# Preamplifier.net
KiCad netlist of a schematic drawn in Altium Designer
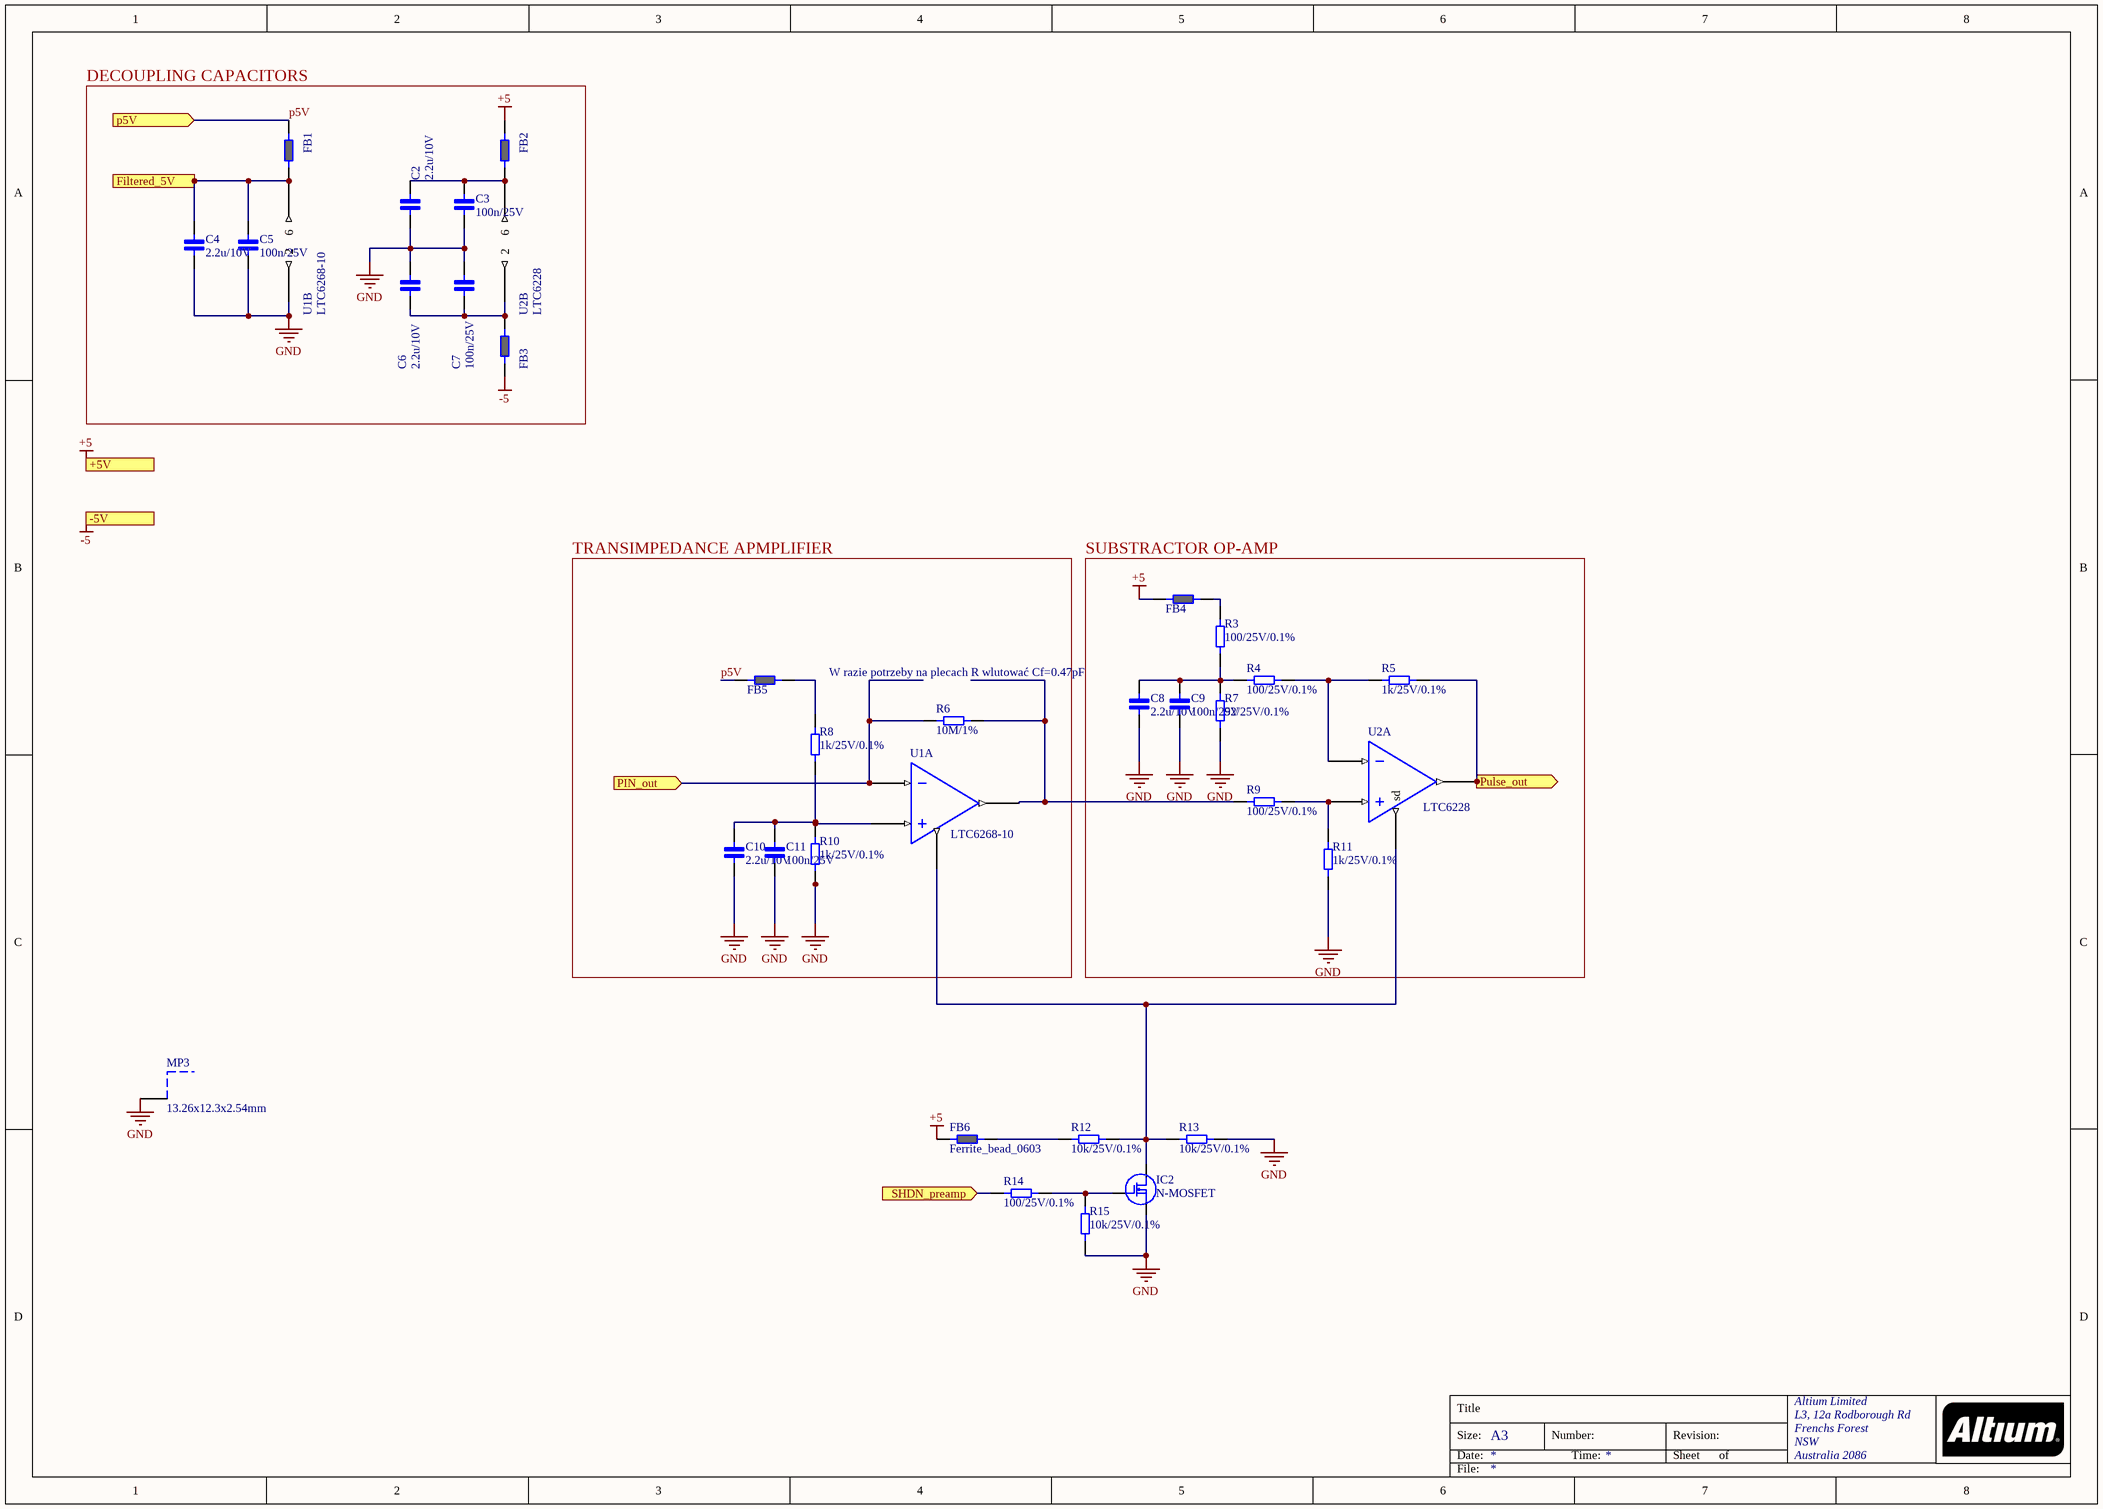
[diagram p0: Preamplifier.SchDoc]

(export (version "E")
  (design (tool "Eeschema 10.0.6"))
  (components
    (comp (ref "C2")
      (value "2.2u/10V")
      (footprint "Cap_0402")
      (description "Ceramic Capacitor 2.2uF / 0402 / 10V / ±5%, Wurth Elektronik MLCC")
      (libsource (lib "Cubesat_lib") (part "Cap_0402_2.2u"))
    )
    (comp (ref "C3")
      (value "100n/25V")
      (footprint "Cap_0402")
      (description "Ceramic Capacitor 100n / 0402 / 25V / ±5%, Wurth Elektronik MLCC")
      (libsource (lib "Cubesat_lib") (part "Cap_0402_100n"))
    )
    (comp (ref "C4")
      (value "2.2u/10V")
      (footprint "Cap_0402")
      (description "Ceramic Capacitor 2.2uF / 0402 / 10V / ±5%, Wurth Elektronik MLCC")
      (libsource (lib "Cubesat_lib") (part "Cap_0402_2.2u"))
    )
    (comp (ref "C5")
      (value "100n/25V")
      (footprint "Cap_0402")
      (description "Ceramic Capacitor 100n / 0402 / 25V / ±5%, Wurth Elektronik MLCC")
      (libsource (lib "Cubesat_lib") (part "Cap_0402_100n"))
    )
    (comp (ref "C6")
      (value "2.2u/10V")
      (footprint "Cap_0402")
      (description "Ceramic Capacitor 2.2uF / 0402 / 10V / ±5%, Wurth Elektronik MLCC")
      (libsource (lib "Cubesat_lib") (part "Cap_0402_2.2u"))
    )
    (comp (ref "C7")
      (value "100n/25V")
      (footprint "Cap_0402")
      (description "Ceramic Capacitor 100n / 0402 / 25V / ±5%, Wurth Elektronik MLCC")
      (libsource (lib "Cubesat_lib") (part "Cap_0402_100n"))
    )
    (comp (ref "C8")
      (value "2.2u/10V")
      (footprint "Cap_0402")
      (description "Ceramic Capacitor 2.2uF / 0402 / 10V / ±5%, Wurth Elektronik MLCC")
      (libsource (lib "Cubesat_lib") (part "Cap_0402_2.2u"))
    )
    (comp (ref "C9")
      (value "100n/25V")
      (footprint "Cap_0402")
      (description "Ceramic Capacitor 100n / 0402 / 25V / ±5%, Wurth Elektronik MLCC")
      (libsource (lib "Cubesat_lib") (part "Cap_0402_100n"))
    )
    (comp (ref "C10")
      (value "2.2u/10V")
      (footprint "Cap_0402")
      (description "Ceramic Capacitor 2.2uF / 0402 / 10V / ±5%, Wurth Elektronik MLCC")
      (libsource (lib "Cubesat_lib") (part "Cap_0402_2.2u"))
    )
    (comp (ref "C11")
      (value "100n/25V")
      (footprint "Cap_0402")
      (description "Ceramic Capacitor 100n / 0402 / 25V / ±5%, Wurth Elektronik MLCC")
      (libsource (lib "Cubesat_lib") (part "Cap_0402_100n"))
    )
    (comp (ref "FB1")
      (value "Ferrite_bead_0603")
      (footprint "Ferrite_0603")
      (description "Ferrite bead")
      (libsource (lib "") (part "Ferrite_bead_0603_2"))
    )
    (comp (ref "FB2")
      (value "Ferrite_bead_0603")
      (footprint "Ferrite_0603")
      (description "Ferrite bead")
      (libsource (lib "") (part "Ferrite_bead_0603_2"))
    )
    (comp (ref "FB3")
      (value "Ferrite_bead_0603")
      (footprint "Ferrite_0603")
      (description "Ferrite bead")
      (libsource (lib "") (part "Ferrite_bead_0603_2"))
    )
    (comp (ref "FB4")
      (value "Ferrite_bead_0603")
      (footprint "Ferrite_0603")
      (description "Ferrite bead")
      (libsource (lib "") (part "Ferrite_bead_0603_1"))
    )
    (comp (ref "FB5")
      (value "Ferrite_bead_0603")
      (footprint "Ferrite_0603")
      (description "Ferrite bead")
      (libsource (lib "") (part "Ferrite_bead_0603_1"))
    )
    (comp (ref "FB6")
      (value "Ferrite_bead_0603")
      (footprint "Ferrite_0603")
      (description "Ferrite bead")
      (libsource (lib "Cubesat_lib") (part "Ferrite_bead_0603"))
    )
    (comp (ref "IC2")
      (value "N-MOSFET")
      (footprint "SOT23-3")
      (description "n-mosfet 50V, low threshold")
      (fields
        (field (name "MANUFACTURER") "NXP Semiconductors")
        (field (name "MANUFACTURER PART NUMBER") "BF861C")
      )
      (libsource (lib "Cubesat_lib") (part "BSS138K"))
    )
    (comp (ref "MP3")
      (value "13.26x12.3x2.54mm")
      (footprint "3610213126S")
      (description "WE-SHC Shielding Cabinet, SMT Frame, Tin Plated, Tape and Reel, 13.26x12.3x2.54mm")
      (fields
        (field (name "MANUFACTURER") "Wurth Elektronik")
        (field (name "MANUFACTURER PART NUMBER") "3610213126S")
      )
      (libsource (lib "shield") (part "3610213126S"))
    )
    (comp (ref "R3")
      (value "100/25V/0.1%")
      (footprint "RES_0402")
      (description "Vishay, thin film resistor 100/25V/0.1%")
      (libsource (lib "") (part "Res_0402_100_1"))
    )
    (comp (ref "R4")
      (value "100/25V/0.1%")
      (footprint "RES_0402")
      (description "Vishay, thin film resistor 100/25V/0.1%")
      (libsource (lib "Cubesat_lib") (part "Res_0402_100"))
    )
    (comp (ref "R5")
      (value "1k/25V/0.1%")
      (footprint "RES_0402")
      (description "Vishay, thin film resistor 1k/25V/0.1%")
      (libsource (lib "") (part "Res_0402_1k_1"))
    )
    (comp (ref "R6")
      (value "10M/1%")
      (footprint "RES_1206_prec")
      (description "Res Thin Film 1206 10M Ohm 0.1% 0.33W(1/3W) ±50ppm/C Sulfur Resistant Pad SMD T/R")
      (fields
        (field (name "MANUFACTURER") "Vishay Dale")
        (field (name "MANUFACTURER PART NUMBER") "P1206H1005BGT")
      )
      (libsource (lib "Cubesat_lib") (part "Prec_res_10M"))
    )
    (comp (ref "R7")
      (value "92/25V/0.1%")
      (footprint "RES_0402")
      (description "Vishay, thin film resistor 92/25V/0.1%")
      (libsource (lib "Cubesat_lib") (part "Res_0402_92"))
    )
    (comp (ref "R8")
      (value "1k/25V/0.1%")
      (footprint "RES_0402")
      (description "Vishay, thin film resistor 1k/25V/0.1%")
      (libsource (lib "Cubesat_lib") (part "Res_0402_1k"))
    )
    (comp (ref "R9")
      (value "100/25V/0.1%")
      (footprint "RES_0402")
      (description "Vishay, thin film resistor 100/25V/0.1%")
      (libsource (lib "Cubesat_lib") (part "Res_0402_100"))
    )
    (comp (ref "R10")
      (value "1k/25V/0.1%")
      (footprint "RES_0402")
      (description "Vishay, thin film resistor 1k/25V/0.1%")
      (libsource (lib "Cubesat_lib") (part "Res_0402_1k"))
    )
    (comp (ref "R11")
      (value "1k/25V/0.1%")
      (footprint "RES_0402")
      (description "Vishay, thin film resistor 1k/25V/0.1%")
      (libsource (lib "Cubesat_lib") (part "Res_0402_1k"))
    )
    (comp (ref "R12")
      (value "10k/25V/0.1%")
      (footprint "RES_0402")
      (description "Vishay, thin film resistor 10k/25V/0.1%")
      (libsource (lib "Cubesat_lib") (part "Res_0402_10k"))
    )
    (comp (ref "R13")
      (value "10k/25V/0.1%")
      (footprint "RES_0402")
      (description "Vishay, thin film resistor 10k/25V/0.1%")
      (libsource (lib "Cubesat_lib") (part "Res_0402_10k"))
    )
    (comp (ref "R14")
      (value "100/25V/0.1%")
      (footprint "RES_0402")
      (description "Vishay, thin film resistor 100/25V/0.1%")
      (libsource (lib "Cubesat_lib") (part "Res_0402_100"))
    )
    (comp (ref "R15")
      (value "10k/25V/0.1%")
      (footprint "RES_0402")
      (description "Vishay, thin film resistor 10k/25V/0.1%")
      (libsource (lib "") (part "Res_0402_10k_1"))
    )
    (comp (ref "U1")
      (value "LTC6268-10")
      (footprint "SOT-23-6")
      (description "4 ghz, ultra-low noise opamp")
      (libsource (lib "Cubesat_lib") (part "LTC6268"))
    )
    (comp (ref "U2")
      (value "LTC6228")
      (footprint "SOT-23-6")
      (description "0.88nV/√Hz 730MHz, 500V/µs,\r\nLow Distortion Rail-to-Rail Output Op\r\nAmps with Shutdown")
      (libsource (lib "Cubesat_lib") (part "LTC6228"))
    )
  )
  (nets
    (net (code "1") (name "+5") (class "Default")
      (node (ref "FB2") (pin "2") (pinfunction "2_2") (pintype "passive"))
      (node (ref "FB4") (pin "2") (pinfunction "2_2") (pintype "passive"))
      (node (ref "FB6") (pin "1") (pinfunction "1_1") (pintype "passive"))
    )
    (net (code "2") (name "-5") (class "Default")
      (node (ref "FB3") (pin "1") (pinfunction "1_1") (pintype "passive"))
    )
    (net (code "3") (name "/Filtered_5V") (class "Default")
      (node (ref "C4") (pin "2") (pinfunction "2_2") (pintype "passive"))
      (node (ref "C5") (pin "2") (pinfunction "2_2") (pintype "passive"))
      (node (ref "FB1") (pin "1") (pinfunction "1_1") (pintype "passive"))
      (node (ref "U1") (pin "6") (pinfunction "6_6") (pintype "output"))
    )
    (net (code "4") (name "/PIN_out") (class "Default")
      (node (ref "R6") (pin "1") (pinfunction "1_1") (pintype "passive"))
      (node (ref "U1") (pin "4") (pinfunction "4_4") (pintype "input"))
    )
    (net (code "5") (name "/Pulse_out") (class "Default")
      (node (ref "R5") (pin "2") (pinfunction "2_2") (pintype "passive"))
      (node (ref "U2") (pin "1") (pinfunction "1_1") (pintype "output"))
    )
    (net (code "6") (name "/SHDN_preamp") (class "Default")
      (node (ref "R14") (pin "1") (pinfunction "1_1") (pintype "passive"))
    )
    (net (code "7") (name "/p5V") (class "Default")
      (node (ref "FB1") (pin "2") (pinfunction "2_2") (pintype "passive"))
      (node (ref "FB5") (pin "2") (pinfunction "2_2") (pintype "passive"))
    )
    (net (code "8") (name "GND") (class "Default")
      (node (ref "C10") (pin "1") (pinfunction "1_1") (pintype "passive"))
      (node (ref "C11") (pin "1") (pinfunction "1_1") (pintype "passive"))
      (node (ref "C2") (pin "1") (pinfunction "1_1") (pintype "passive"))
      (node (ref "C3") (pin "1") (pinfunction "1_1") (pintype "passive"))
      (node (ref "C4") (pin "1") (pinfunction "1_1") (pintype "passive"))
      (node (ref "C5") (pin "1") (pinfunction "1_1") (pintype "passive"))
      (node (ref "C6") (pin "2") (pinfunction "2_2") (pintype "passive"))
      (node (ref "C7") (pin "2") (pinfunction "2_2") (pintype "passive"))
      (node (ref "C8") (pin "1") (pinfunction "1_1") (pintype "passive"))
      (node (ref "C9") (pin "1") (pinfunction "1_1") (pintype "passive"))
      (node (ref "IC2") (pin "2") (pinfunction "S_2") (pintype "passive"))
      (node (ref "MP3") (pin "1") (pinfunction "1_1") (pintype "passive"))
      (node (ref "R10") (pin "1") (pinfunction "1_1") (pintype "passive"))
      (node (ref "R11") (pin "1") (pinfunction "1_1") (pintype "passive"))
      (node (ref "R13") (pin "2") (pinfunction "2_2") (pintype "passive"))
      (node (ref "R15") (pin "1") (pinfunction "1_1") (pintype "passive"))
      (node (ref "R7") (pin "1") (pinfunction "1_1") (pintype "passive"))
      (node (ref "U1") (pin "2") (pinfunction "2_2") (pintype "output"))
    )
    (net (code "9") (name "Net-(C2-Pad2)") (class "Default")
      (node (ref "C2") (pin "2") (pinfunction "2_2") (pintype "passive"))
      (node (ref "C3") (pin "2") (pinfunction "2_2") (pintype "passive"))
      (node (ref "FB2") (pin "1") (pinfunction "1_1") (pintype "passive"))
      (node (ref "U2") (pin "6") (pinfunction "6_6") (pintype "output"))
    )
    (net (code "10") (name "Net-(C6-Pad1)") (class "Default")
      (node (ref "C6") (pin "1") (pinfunction "1_1") (pintype "passive"))
      (node (ref "C7") (pin "1") (pinfunction "1_1") (pintype "passive"))
      (node (ref "FB3") (pin "2") (pinfunction "2_2") (pintype "passive"))
      (node (ref "U2") (pin "2") (pinfunction "2_2") (pintype "output"))
    )
    (net (code "11") (name "Net-(C8-Pad2)") (class "Default")
      (node (ref "C8") (pin "2") (pinfunction "2_2") (pintype "passive"))
      (node (ref "C9") (pin "2") (pinfunction "2_2") (pintype "passive"))
      (node (ref "R3") (pin "1") (pinfunction "1_1") (pintype "passive"))
      (node (ref "R4") (pin "1") (pinfunction "1_1") (pintype "passive"))
      (node (ref "R7") (pin "2") (pinfunction "2_2") (pintype "passive"))
    )
    (net (code "12") (name "Net-(C10-Pad2)") (class "Default")
      (node (ref "C10") (pin "2") (pinfunction "2_2") (pintype "passive"))
      (node (ref "C11") (pin "2") (pinfunction "2_2") (pintype "passive"))
      (node (ref "R10") (pin "2") (pinfunction "2_2") (pintype "passive"))
      (node (ref "R8") (pin "1") (pinfunction "1_1") (pintype "passive"))
      (node (ref "U1") (pin "3") (pinfunction "3_3") (pintype "input"))
    )
    (net (code "13") (name "Net-(FB4-Pad1)") (class "Default")
      (node (ref "FB4") (pin "1") (pinfunction "1_1") (pintype "passive"))
      (node (ref "R3") (pin "2") (pinfunction "2_2") (pintype "passive"))
    )
    (net (code "14") (name "Net-(FB5-Pad1)") (class "Default")
      (node (ref "FB5") (pin "1") (pinfunction "1_1") (pintype "passive"))
      (node (ref "R8") (pin "2") (pinfunction "2_2") (pintype "passive"))
    )
    (net (code "15") (name "Net-(FB6-Pad2)") (class "Default")
      (node (ref "FB6") (pin "2") (pinfunction "2_2") (pintype "passive"))
      (node (ref "R12") (pin "1") (pinfunction "1_1") (pintype "passive"))
    )
    (net (code "16") (name "Net-(IC2-D)") (class "Default")
      (node (ref "IC2") (pin "3") (pinfunction "D_3") (pintype "passive"))
      (node (ref "R12") (pin "2") (pinfunction "2_2") (pintype "passive"))
      (node (ref "R13") (pin "1") (pinfunction "1_1") (pintype "passive"))
      (node (ref "U1") (pin "5") (pinfunction "sd_5") (pintype "output"))
      (node (ref "U2") (pin "5") (pinfunction "sd_5") (pintype "output"))
    )
    (net (code "17") (name "Net-(IC2-G)") (class "Default")
      (node (ref "IC2") (pin "1") (pinfunction "G_1") (pintype "passive"))
      (node (ref "R14") (pin "2") (pinfunction "2_2") (pintype "passive"))
      (node (ref "R15") (pin "2") (pinfunction "2_2") (pintype "passive"))
    )
    (net (code "18") (name "Net-(R4-Pad2)") (class "Default")
      (node (ref "R4") (pin "2") (pinfunction "2_2") (pintype "passive"))
      (node (ref "R5") (pin "1") (pinfunction "1_1") (pintype "passive"))
      (node (ref "U2") (pin "4") (pinfunction "4_4") (pintype "input"))
    )
    (net (code "19") (name "Net-(R6-Pad2)") (class "Default")
      (node (ref "R6") (pin "2") (pinfunction "2_2") (pintype "passive"))
      (node (ref "R9") (pin "1") (pinfunction "1_1") (pintype "passive"))
      (node (ref "U1") (pin "1") (pinfunction "1_1") (pintype "output"))
    )
    (net (code "20") (name "Net-(R11-Pad2)") (class "Default")
      (node (ref "R11") (pin "2") (pinfunction "2_2") (pintype "passive"))
      (node (ref "R9") (pin "2") (pinfunction "2_2") (pintype "passive"))
      (node (ref "U2") (pin "3") (pinfunction "3_3") (pintype "input"))
    )
  )
)
